# xv11_lidar_controller.net
KiCad netlist of a schematic drawn in EAGLE
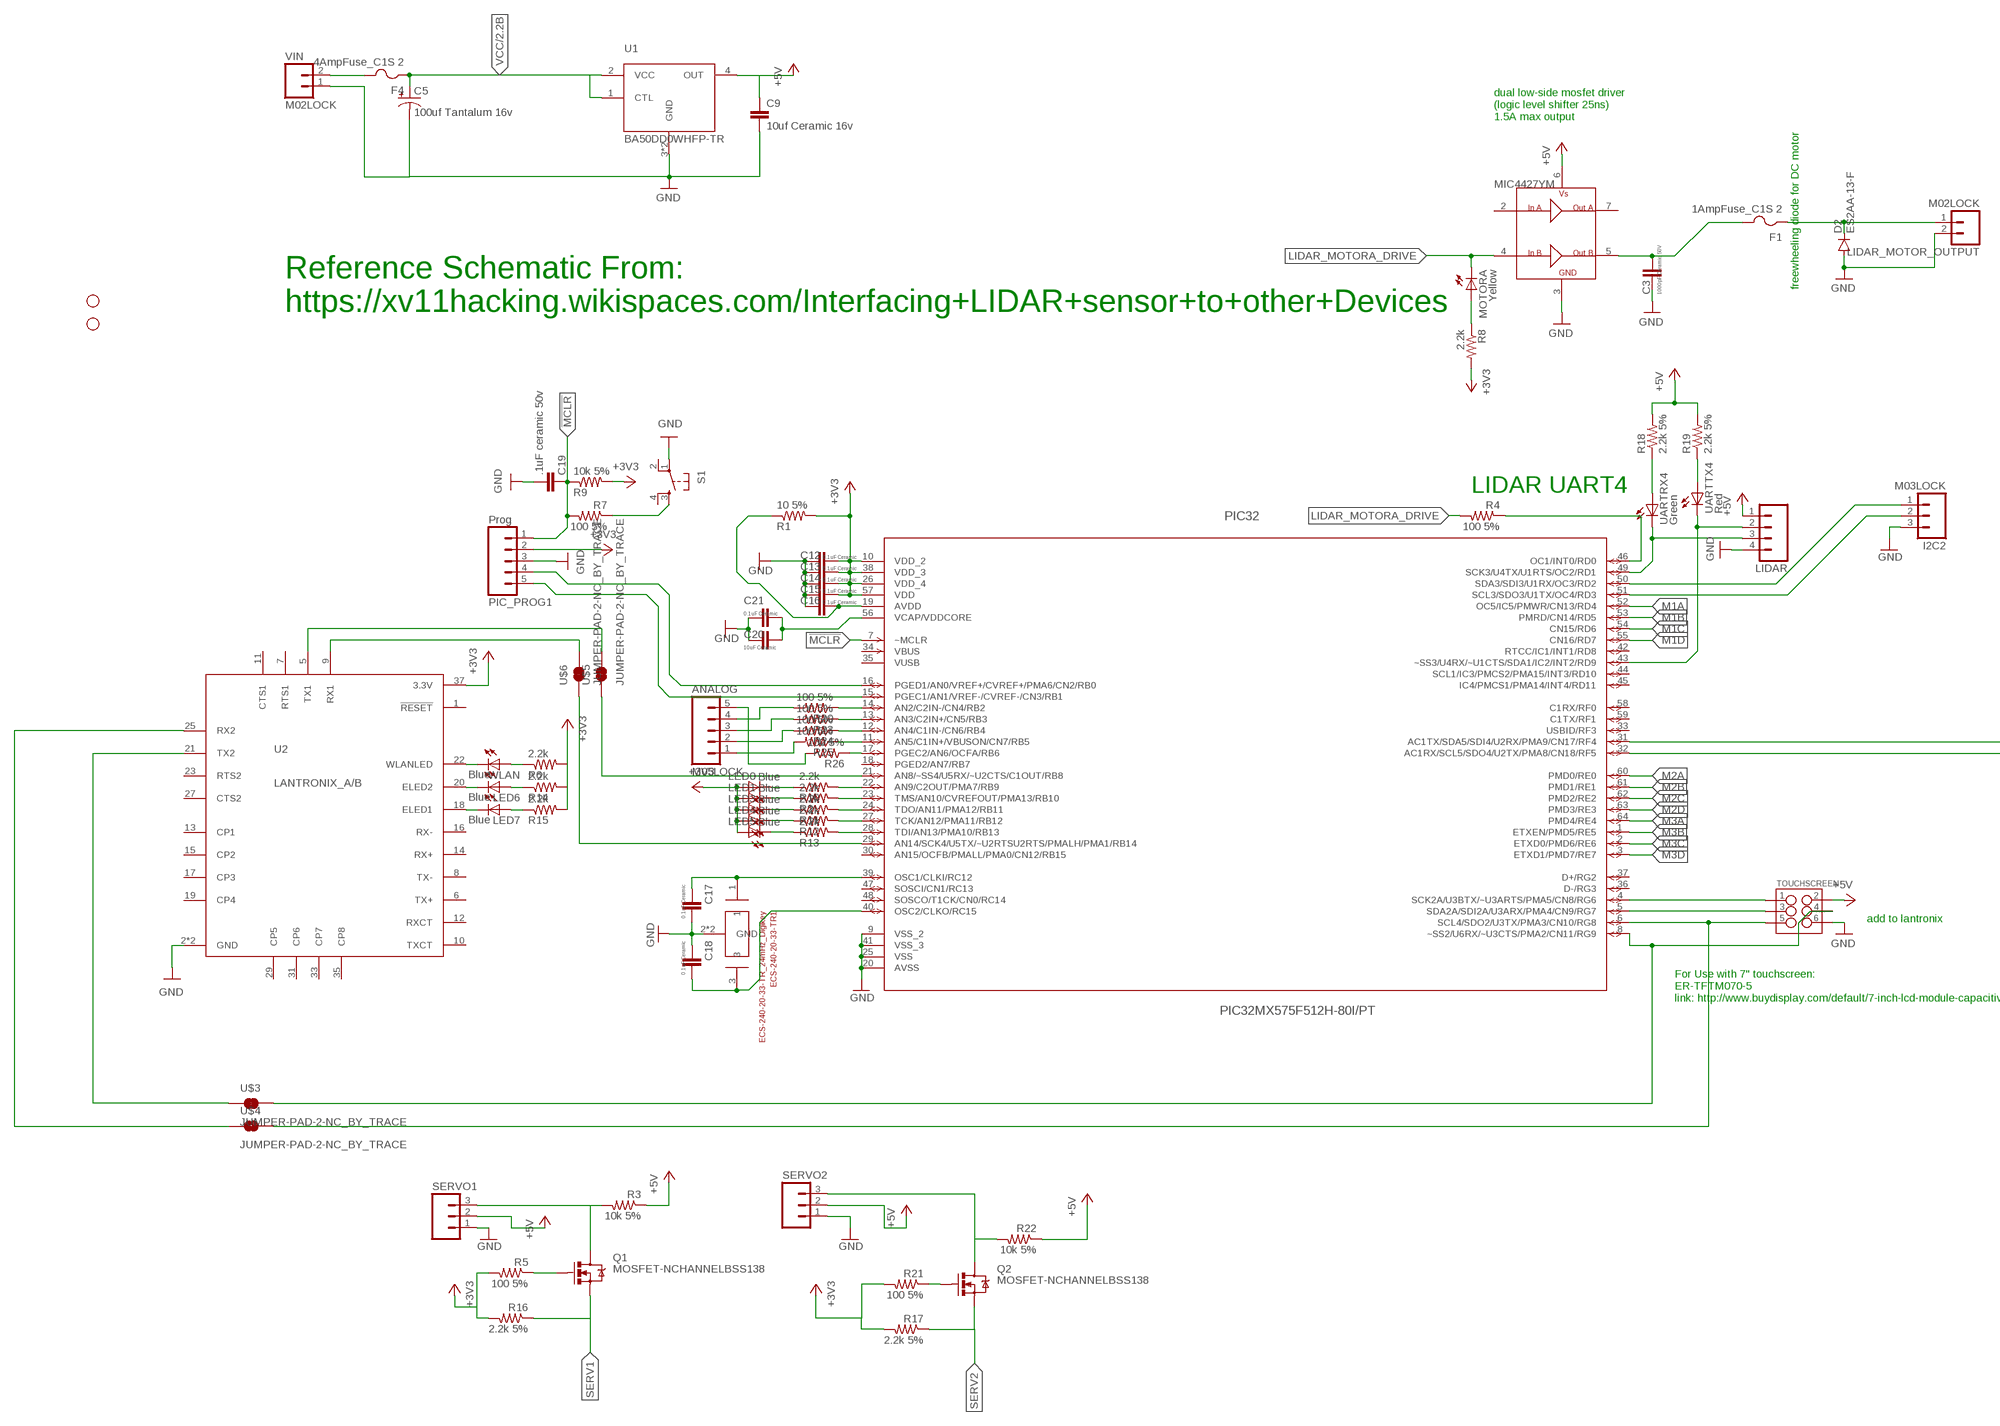
[diagram p0: schematic, sheet 1, part 1 of 2]
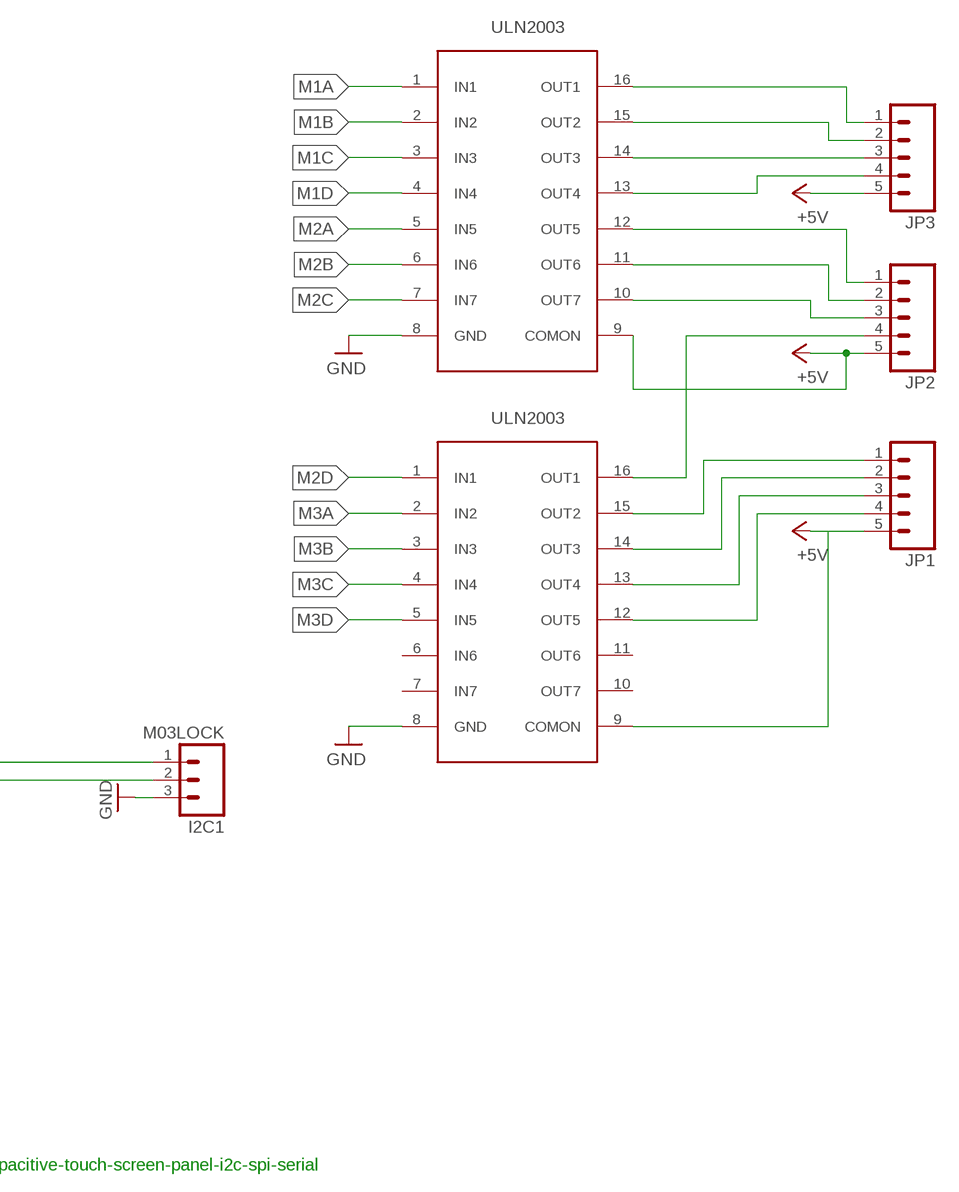
[diagram p1: schematic, sheet 1, part 2 of 2]
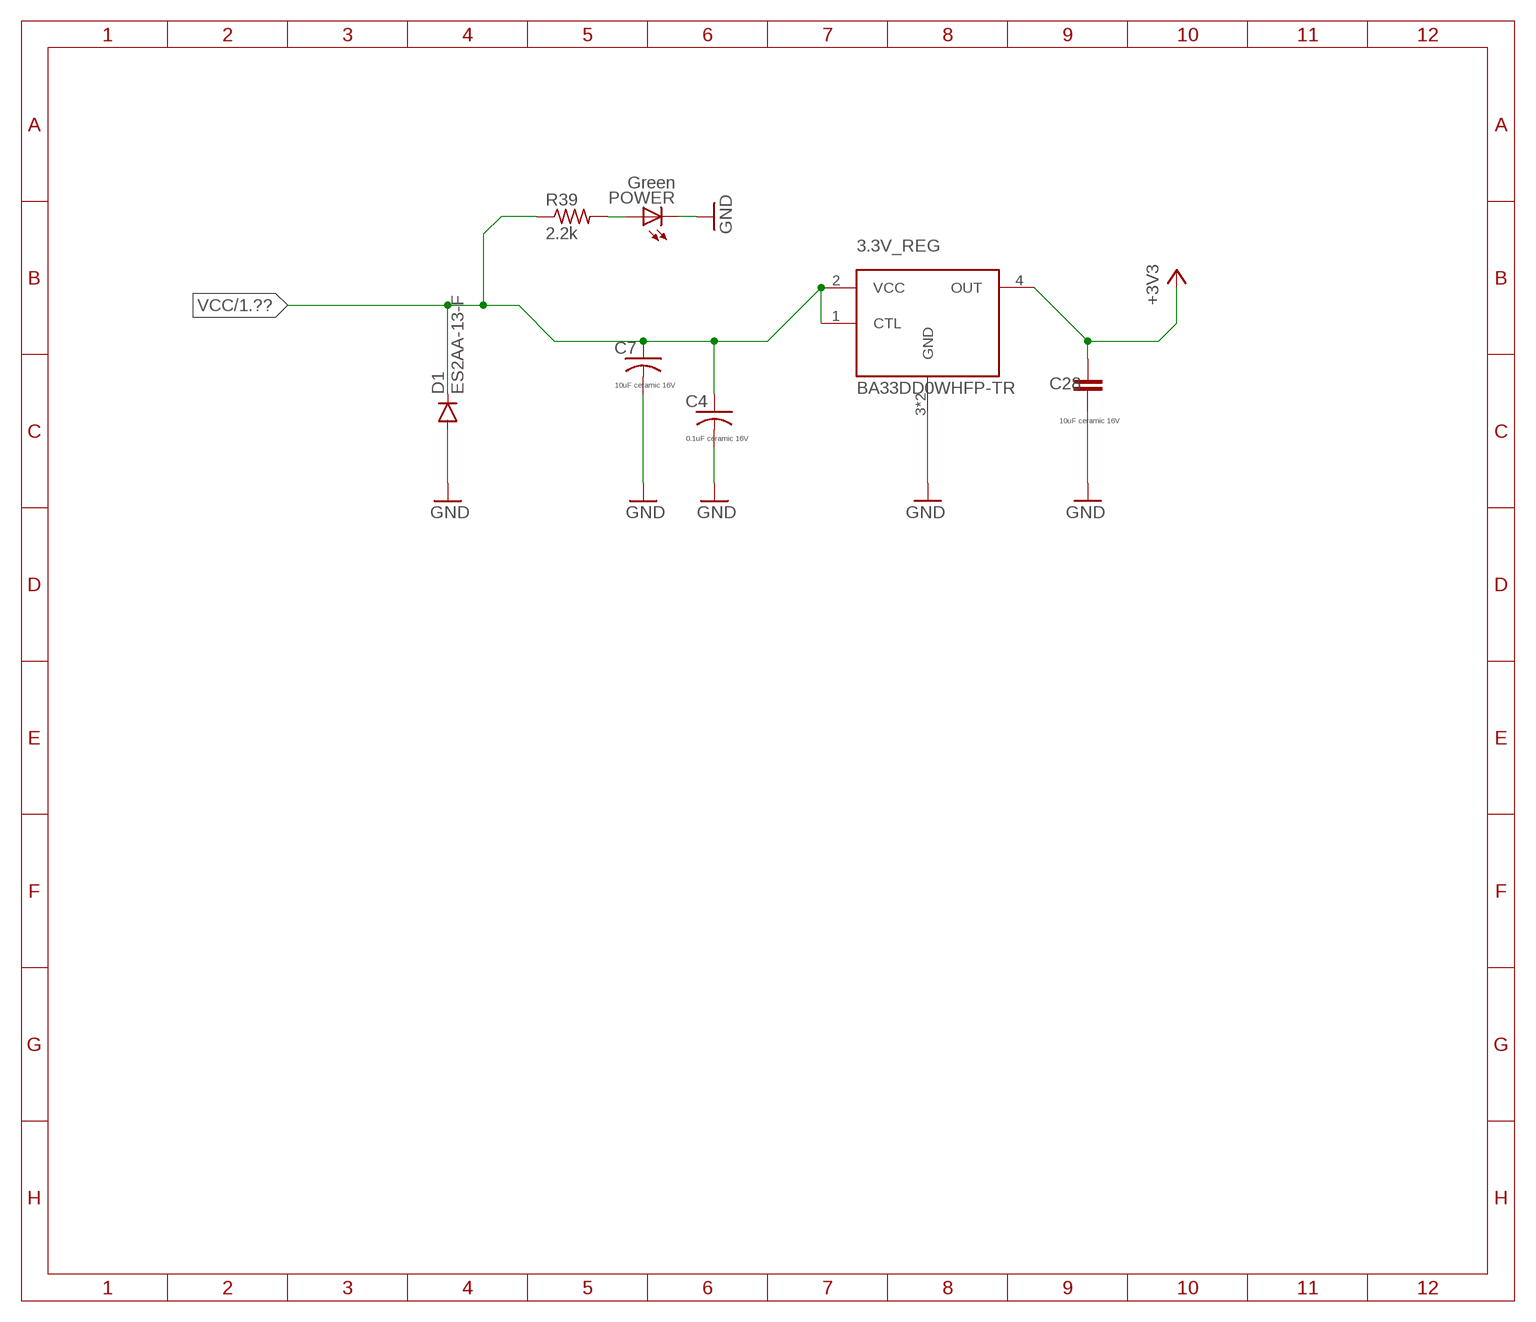
[diagram p2: schematic, sheet 2]

(export (version "E")
  (design (tool "Eeschema 10.0.6"))
  (components
    (comp (ref "3.3V_REG")
      (value "BA33DD0WHFP-TR")
      (footprint "eagle-import:HRP5")
      (libsource (lib "eagle-import") (part "BA50DD0WHFP-TR"))
    )
    (comp (ref "C4")
      (value "0.1uF ceramic 16V")
      (footprint "eagle-import:C0805K")
      (libsource (lib "eagle-import") (part "C-USC0805K"))
    )
    (comp (ref "C7")
      (value "10uF ceramic 16V")
      (footprint "eagle-import:C0805K")
      (libsource (lib "eagle-import") (part "C-USC0805K"))
    )
    (comp (ref "C28")
      (value "10uF ceramic 16V")
      (footprint "eagle-import:0805")
      (libsource (lib "eagle-import") (part "CAP0805"))
    )
    (comp (ref "D1")
      (value "ES2AA-13-F")
      (footprint "eagle-import:SMA-DIODE")
      (libsource (lib "eagle-import") (part "DIODESMA"))
    )
    (comp (ref "POWER")
      (value "Green")
      (footprint "eagle-import:CHIP-LED0805")
      (libsource (lib "eagle-import") (part "LEDCHIP-LED0805"))
    )
    (comp (ref "R39")
      (value "2.2k")
      (footprint "eagle-import:R0805")
      (libsource (lib "eagle-import") (part "R-US_R0805"))
    )
    (comp (ref "ANALOG")
      (value "M05LOCK")
      (footprint "eagle-import:1X05_LOCK")
      (libsource (lib "eagle-import") (part "M05LOCK"))
    )
    (comp (ref "C3")
      (value "1000pF Ceramic 50V")
      (footprint "eagle-import:0805")
      (libsource (lib "eagle-import") (part "CAP0805"))
    )
    (comp (ref "C5")
      (value "100uf Tantalum 16v")
      (footprint "eagle-import:EIA3216")
      (libsource (lib "eagle-import") (part "CAP_POL1206"))
    )
    (comp (ref "C9")
      (value "10uf Ceramic 16v")
      (footprint "eagle-import:0805")
      (libsource (lib "eagle-import") (part "CAP0805"))
    )
    (comp (ref "C12")
      (value "0.1uF Ceramic")
      (footprint "eagle-import:0805")
      (libsource (lib "eagle-import") (part "CAP0805"))
    )
    (comp (ref "C13")
      (value "0.1uF Ceramic")
      (footprint "eagle-import:0805")
      (libsource (lib "eagle-import") (part "CAP0805"))
    )
    (comp (ref "C14")
      (value "0.1uF Ceramic")
      (footprint "eagle-import:0805")
      (libsource (lib "eagle-import") (part "CAP0805"))
    )
    (comp (ref "C15")
      (value "0.1uF Ceramic")
      (footprint "eagle-import:0805")
      (libsource (lib "eagle-import") (part "CAP0805"))
    )
    (comp (ref "C16")
      (value "0.1uF Ceramic")
      (footprint "eagle-import:0805")
      (libsource (lib "eagle-import") (part "CAP0805"))
    )
    (comp (ref "C17")
      (value "0.1uF Ceramic")
      (footprint "eagle-import:0805")
      (libsource (lib "eagle-import") (part "CAP0805"))
    )
    (comp (ref "C18")
      (value "0.1uF Ceramic")
      (footprint "eagle-import:0805")
      (libsource (lib "eagle-import") (part "CAP0805"))
    )
    (comp (ref "C19")
      (value ".1uF ceramic 50v")
      (footprint "eagle-import:0805")
      (libsource (lib "eagle-import") (part "1UF-25V-10%(0805)"))
    )
    (comp (ref "C20")
      (value "10uF Ceramic")
      (footprint "eagle-import:0805")
      (libsource (lib "eagle-import") (part "CAP0805"))
    )
    (comp (ref "C21")
      (value "0.1uF Ceramic")
      (footprint "eagle-import:0805")
      (libsource (lib "eagle-import") (part "CAP0805"))
    )
    (comp (ref "D2")
      (value "ES2AA-13-F")
      (footprint "eagle-import:SMA-DIODE")
      (libsource (lib "eagle-import") (part "DIODESMA"))
    )
    (comp (ref "ECS-240-20-33-TR1")
      (value "ECS-240-20-33-TR_24mHz_Digikey")
      (footprint "eagle-import:ECX-32")
      (libsource (lib "eagle-import") (part "CRYSTAL"))
    )
    (comp (ref "F1")
      (value "1AmpFuse_C1S 2")
      (footprint "eagle-import:R1206")
      (libsource (lib "eagle-import") (part "PTCFUSE-1206"))
    )
    (comp (ref "F4")
      (value "4AmpFuse_C1S 2")
      (footprint "eagle-import:R1206")
      (libsource (lib "eagle-import") (part "PTCFUSE-1206"))
    )
    (comp (ref "I2C1")
      (value "M03LOCK")
      (footprint "eagle-import:1X03_LOCK")
      (libsource (lib "eagle-import") (part "M03LOCK"))
    )
    (comp (ref "I2C2")
      (value "M03LOCK")
      (footprint "eagle-import:1X03_LOCK")
      (libsource (lib "eagle-import") (part "M03LOCK"))
    )
    (comp (ref "JP1")
      (value "M05LOCK")
      (footprint "eagle-import:1X05_LOCK")
      (libsource (lib "eagle-import") (part "M05LOCK"))
    )
    (comp (ref "JP2")
      (value "M05LOCK")
      (footprint "eagle-import:1X05_LOCK")
      (libsource (lib "eagle-import") (part "M05LOCK"))
    )
    (comp (ref "JP3")
      (value "M05LOCK")
      (footprint "eagle-import:1X05_LOCK")
      (libsource (lib "eagle-import") (part "M05LOCK"))
    )
    (comp (ref "LED0")
      (value "Blue")
      (footprint "eagle-import:CHIP-LED0805")
      (libsource (lib "eagle-import") (part "LEDCHIP-LED0805"))
    )
    (comp (ref "LED1")
      (value "Blue")
      (footprint "eagle-import:CHIP-LED0805")
      (libsource (lib "eagle-import") (part "LEDCHIP-LED0805"))
    )
    (comp (ref "LED3")
      (value "Blue")
      (footprint "eagle-import:CHIP-LED0805")
      (libsource (lib "eagle-import") (part "LEDCHIP-LED0805"))
    )
    (comp (ref "LED4")
      (value "Blue")
      (footprint "eagle-import:CHIP-LED0805")
      (libsource (lib "eagle-import") (part "LEDCHIP-LED0805"))
    )
    (comp (ref "LED5")
      (value "Blue")
      (footprint "eagle-import:CHIP-LED0805")
      (libsource (lib "eagle-import") (part "LEDCHIP-LED0805"))
    )
    (comp (ref "LED6")
      (value "Blue")
      (footprint "eagle-import:CHIP-LED0805")
      (libsource (lib "eagle-import") (part "LEDCHIP-LED0805"))
    )
    (comp (ref "LED7")
      (value "Blue")
      (footprint "eagle-import:CHIP-LED0805")
      (libsource (lib "eagle-import") (part "LEDCHIP-LED0805"))
    )
    (comp (ref "LIDAR")
      (value "M04LOCK")
      (footprint "eagle-import:1X04_LOCK")
      (libsource (lib "eagle-import") (part "M04LOCK"))
    )
    (comp (ref "LIDAR_MOTOR_OUTPUT")
      (value "M02LOCK")
      (footprint "eagle-import:1X02_LOCK")
      (libsource (lib "eagle-import") (part "M02LOCK"))
    )
    (comp (ref "MOTORA")
      (value "Yellow")
      (footprint "eagle-import:CHIP-LED0805")
      (libsource (lib "eagle-import") (part "LEDCHIP-LED0805"))
    )
    (comp (ref "PIC32")
      (value "PIC32MX575F512H-80I/PT")
      (footprint "eagle-import:QFP50P1200X1200X120-64N")
      (fields (field (name "MPN") "PIC32MX675F512H-80I/PT"))
      (libsource (lib "eagle-import") (part "PIC32MX575F512H-80I/PT"))
    )
    (comp (ref "PIC_PROG1")
      (value "Prog")
      (footprint "eagle-import:1X05_LOCK_LONGPADS")
      (libsource (lib "eagle-import") (part "M05LOCK_LONGPADS"))
    )
    (comp (ref "Q1")
      (value "MOSFET-NCHANNELBSS138")
      (footprint "eagle-import:SOT23")
      (libsource (lib "eagle-import") (part "MOSFET-NCHANNELBSS138"))
    )
    (comp (ref "Q2")
      (value "MOSFET-NCHANNELBSS138")
      (footprint "eagle-import:SOT23")
      (libsource (lib "eagle-import") (part "MOSFET-NCHANNELBSS138"))
    )
    (comp (ref "R1")
      (value "10 5%")
      (footprint "eagle-import:R0805")
      (libsource (lib "eagle-import") (part "R-US_R0805"))
    )
    (comp (ref "R2")
      (value "2.2k")
      (footprint "eagle-import:R0805")
      (libsource (lib "eagle-import") (part "R-US_R0805"))
    )
    (comp (ref "R3")
      (value "10k 5%")
      (footprint "eagle-import:R0805")
      (libsource (lib "eagle-import") (part "R-US_R0805"))
    )
    (comp (ref "R4")
      (value "100 5%")
      (footprint "eagle-import:M0805")
      (libsource (lib "eagle-import") (part "R-US_M0805"))
    )
    (comp (ref "R5")
      (value "100 5%")
      (footprint "eagle-import:R0805")
      (libsource (lib "eagle-import") (part "R-US_R0805"))
    )
    (comp (ref "R6")
      (value "2.2k")
      (footprint "eagle-import:R0805")
      (libsource (lib "eagle-import") (part "R-US_R0805"))
    )
    (comp (ref "R7")
      (value "100 5%")
      (footprint "eagle-import:R0805")
      (libsource (lib "eagle-import") (part "R-US_R0805"))
    )
    (comp (ref "R8")
      (value "2.2k")
      (footprint "eagle-import:M0805")
      (libsource (lib "eagle-import") (part "R-US_M0805"))
    )
    (comp (ref "R9")
      (value "10k 5%")
      (footprint "eagle-import:R0805")
      (libsource (lib "eagle-import") (part "R-US_R0805"))
    )
    (comp (ref "R10")
      (value "2.2k")
      (footprint "eagle-import:R0805")
      (libsource (lib "eagle-import") (part "R-US_R0805"))
    )
    (comp (ref "R11")
      (value "2.2k")
      (footprint "eagle-import:R0805")
      (libsource (lib "eagle-import") (part "R-US_R0805"))
    )
    (comp (ref "R12")
      (value "2.2k")
      (footprint "eagle-import:R0805")
      (libsource (lib "eagle-import") (part "R-US_R0805"))
    )
    (comp (ref "R13")
      (value "2.2k")
      (footprint "eagle-import:R0805")
      (libsource (lib "eagle-import") (part "R-US_R0805"))
    )
    (comp (ref "R14")
      (value "2.2k")
      (footprint "eagle-import:R0805")
      (libsource (lib "eagle-import") (part "R-US_R0805"))
    )
    (comp (ref "R15")
      (value "2.2k")
      (footprint "eagle-import:R0805")
      (libsource (lib "eagle-import") (part "R-US_R0805"))
    )
    (comp (ref "R16")
      (value "2.2k 5%")
      (footprint "eagle-import:R0805")
      (libsource (lib "eagle-import") (part "R-US_R0805"))
    )
    (comp (ref "R17")
      (value "2.2k 5%")
      (footprint "eagle-import:R0805")
      (libsource (lib "eagle-import") (part "R-US_R0805"))
    )
    (comp (ref "R18")
      (value "2.2k 5%")
      (footprint "eagle-import:M0805")
      (libsource (lib "eagle-import") (part "R-US_M0805"))
    )
    (comp (ref "R19")
      (value "2.2k 5%")
      (footprint "eagle-import:M0805")
      (libsource (lib "eagle-import") (part "R-US_M0805"))
    )
    (comp (ref "R20")
      (value "100 5%")
      (footprint "eagle-import:R0805")
      (libsource (lib "eagle-import") (part "R-US_R0805"))
    )
    (comp (ref "R21")
      (value "100 5%")
      (footprint "eagle-import:R0805")
      (libsource (lib "eagle-import") (part "R-US_R0805"))
    )
    (comp (ref "R22")
      (value "10k 5%")
      (footprint "eagle-import:R0805")
      (libsource (lib "eagle-import") (part "R-US_R0805"))
    )
    (comp (ref "R23")
      (value "100 5%")
      (footprint "eagle-import:R0805")
      (libsource (lib "eagle-import") (part "R-US_R0805"))
    )
    (comp (ref "R24")
      (value "100 5%")
      (footprint "eagle-import:R0805")
      (libsource (lib "eagle-import") (part "R-US_R0805"))
    )
    (comp (ref "R25")
      (value "100 5%")
      (footprint "eagle-import:R0805")
      (libsource (lib "eagle-import") (part "R-US_R0805"))
    )
    (comp (ref "R26")
      (value "100 5%")
      (footprint "eagle-import:R0805")
      (libsource (lib "eagle-import") (part "R-US_R0805"))
    )
    (comp (ref "S1")
      (value "TAC_SWITCHSMD")
      (footprint "eagle-import:TACTILE-SWITCH-SMD")
      (libsource (lib "eagle-import") (part "TAC_SWITCHSMD"))
    )
    (comp (ref "SERVO1")
      (value "M03PTH")
      (footprint "eagle-import:1X03")
      (libsource (lib "eagle-import") (part "M03PTH"))
    )
    (comp (ref "SERVO2")
      (value "M03PTH")
      (footprint "eagle-import:1X03")
      (libsource (lib "eagle-import") (part "M03PTH"))
    )
    (comp (ref "STANDOFF1")
      (value "STAND-OFF")
      (footprint "eagle-import:STAND-OFF")
      (libsource (lib "eagle-import") (part "STAND-OFF"))
    )
    (comp (ref "STANDOFF2")
      (value "STAND-OFF")
      (footprint "eagle-import:STAND-OFF")
      (libsource (lib "eagle-import") (part "STAND-OFF"))
    )
    (comp (ref "TOUCHSCREEN")
      (value "M03X2NO_SILK")
      (footprint "eagle-import:2X3-NS")
      (libsource (lib "eagle-import") (part "M03X2NO_SILK"))
    )
    (comp (ref "U$1")
      (value "ULN2003")
      (footprint "eagle-import:SOIC16_3.9WIDE")
      (libsource (lib "eagle-import") (part "ULN2003"))
    )
    (comp (ref "U$2")
      (value "ULN2003")
      (footprint "eagle-import:SOIC16_3.9WIDE")
      (libsource (lib "eagle-import") (part "ULN2003"))
    )
    (comp (ref "U$3")
      (value "JUMPER-PAD-2-NC_BY_TRACE")
      (footprint "eagle-import:PAD-JUMPER-2-NC_BY_TRACE_YES_SILK")
      (libsource (lib "eagle-import") (part "JUMPER-PAD-2-NC_BY_TRACE"))
    )
    (comp (ref "U$4")
      (value "JUMPER-PAD-2-NC_BY_TRACE")
      (footprint "eagle-import:PAD-JUMPER-2-NC_BY_TRACE_YES_SILK")
      (libsource (lib "eagle-import") (part "JUMPER-PAD-2-NC_BY_TRACE"))
    )
    (comp (ref "U$5")
      (value "JUMPER-PAD-2-NC_BY_TRACE")
      (footprint "eagle-import:PAD-JUMPER-2-NC_BY_TRACE_YES_SILK")
      (libsource (lib "eagle-import") (part "JUMPER-PAD-2-NC_BY_TRACE"))
    )
    (comp (ref "U$6")
      (value "JUMPER-PAD-2-NC_BY_TRACE")
      (footprint "eagle-import:PAD-JUMPER-2-NC_BY_TRACE_YES_SILK")
      (libsource (lib "eagle-import") (part "JUMPER-PAD-2-NC_BY_TRACE"))
    )
    (comp (ref "U1")
      (value "BA50DD0WHFP-TR")
      (footprint "eagle-import:HRP5")
      (libsource (lib "eagle-import") (part "BA50DD0WHFP-TR"))
    )
    (comp (ref "U2")
      (value "LANTRONIX_A/B")
      (footprint "eagle-import:LANA_BTH")
      (libsource (lib "eagle-import") (part "LANTRONIX_A/B"))
    )
    (comp (ref "U3")
      (value "MIC4427YM")
      (footprint "eagle-import:SO-08")
      (libsource (lib "eagle-import") (part "MIC4427YM"))
    )
    (comp (ref "UARTRX4")
      (value "Green")
      (footprint "eagle-import:CHIP-LED0805")
      (libsource (lib "eagle-import") (part "LEDCHIP-LED0805"))
    )
    (comp (ref "UARTTX4")
      (value "Red")
      (footprint "eagle-import:CHIP-LED0805")
      (libsource (lib "eagle-import") (part "LEDCHIP-LED0805"))
    )
    (comp (ref "VIN")
      (value "M02LOCK")
      (footprint "eagle-import:1X02_LOCK")
      (libsource (lib "eagle-import") (part "M02LOCK"))
    )
    (comp (ref "WLAN")
      (value "Blue")
      (footprint "eagle-import:CHIP-LED0805")
      (libsource (lib "eagle-import") (part "LEDCHIP-LED0805"))
    )
  )
  (nets
    (net (code "1") (name "+3V3") (class "Default")
      (node (ref "3.3V_REG") (pin "4") (pinfunction "OUT_4") (pintype "bidirectional"))
      (node (ref "C12") (pin "2") (pinfunction "2_2") (pintype "passive"))
      (node (ref "C13") (pin "2") (pinfunction "2_2") (pintype "passive"))
      (node (ref "C14") (pin "2") (pinfunction "2_2") (pintype "passive"))
      (node (ref "C15") (pin "2") (pinfunction "2_2") (pintype "passive"))
      (node (ref "C28") (pin "1") (pinfunction "1_1") (pintype "passive"))
      (node (ref "LED0") (pin "A") (pinfunction "A_A") (pintype "passive"))
      (node (ref "LED1") (pin "A") (pinfunction "A_A") (pintype "passive"))
      (node (ref "LED3") (pin "A") (pinfunction "A_A") (pintype "passive"))
      (node (ref "LED4") (pin "A") (pinfunction "A_A") (pintype "passive"))
      (node (ref "LED5") (pin "A") (pinfunction "A_A") (pintype "passive"))
      (node (ref "PIC32") (pin "10") (pinfunction "VDD_2_10") (pintype "power_in"))
      (node (ref "PIC32") (pin "26") (pinfunction "VDD_4_26") (pintype "power_in"))
      (node (ref "PIC32") (pin "38") (pinfunction "VDD_3_38") (pintype "power_in"))
      (node (ref "PIC32") (pin "57") (pinfunction "VDD_57") (pintype "power_in"))
      (node (ref "PIC_PROG1") (pin "2") (pinfunction "2_2") (pintype "passive"))
      (node (ref "R1") (pin "2") (pinfunction "2_2") (pintype "passive"))
      (node (ref "R14") (pin "2") (pinfunction "2_2") (pintype "passive"))
      (node (ref "R15") (pin "2") (pinfunction "2_2") (pintype "passive"))
      (node (ref "R16") (pin "2") (pinfunction "2_2") (pintype "passive"))
      (node (ref "R17") (pin "2") (pinfunction "2_2") (pintype "passive"))
      (node (ref "R21") (pin "2") (pinfunction "2_2") (pintype "passive"))
      (node (ref "R5") (pin "2") (pinfunction "2_2") (pintype "passive"))
      (node (ref "R6") (pin "2") (pinfunction "2_2") (pintype "passive"))
      (node (ref "R8") (pin "2") (pinfunction "2_2") (pintype "passive"))
      (node (ref "R9") (pin "2") (pinfunction "2_2") (pintype "passive"))
      (node (ref "U2") (pin "37") (pinfunction "3.3V_37") (pintype "bidirectional"))
    )
    (net (code "2") (name "+5V") (class "Default")
      (node (ref "C9") (pin "1") (pinfunction "1_1") (pintype "passive"))
      (node (ref "JP1") (pin "5") (pinfunction "5_5") (pintype "passive"))
      (node (ref "JP2") (pin "5") (pinfunction "5_5") (pintype "passive"))
      (node (ref "JP3") (pin "5") (pinfunction "5_5") (pintype "passive"))
      (node (ref "LIDAR") (pin "1") (pinfunction "1_1") (pintype "passive"))
      (node (ref "R18") (pin "2") (pinfunction "2_2") (pintype "passive"))
      (node (ref "R19") (pin "2") (pinfunction "2_2") (pintype "passive"))
      (node (ref "R22") (pin "1") (pinfunction "1_1") (pintype "passive"))
      (node (ref "R3") (pin "1") (pinfunction "1_1") (pintype "passive"))
      (node (ref "SERVO1") (pin "2") (pinfunction "2_2") (pintype "passive"))
      (node (ref "SERVO2") (pin "2") (pinfunction "2_2") (pintype "passive"))
      (node (ref "TOUCHSCREEN") (pin "2") (pinfunction "2_2") (pintype "bidirectional"))
      (node (ref "U$1") (pin "9") (pinfunction "COMON_9") (pintype "bidirectional"))
      (node (ref "U$2") (pin "9") (pinfunction "COMON_9") (pintype "bidirectional"))
      (node (ref "U1") (pin "4") (pinfunction "OUT_4") (pintype "bidirectional"))
      (node (ref "U3") (pin "6") (pinfunction "VS_6") (pintype "bidirectional"))
    )
    (net (code "3") (name "GND") (class "Default")
      (node (ref "3.3V_REG") (pin "3") (pinfunction "GND_3") (pintype "bidirectional"))
      (node (ref "3.3V_REG") (pin "G") (pinfunction "GND_G") (pintype "bidirectional"))
      (node (ref "C12") (pin "1") (pinfunction "1_1") (pintype "passive"))
      (node (ref "C13") (pin "1") (pinfunction "1_1") (pintype "passive"))
      (node (ref "C14") (pin "1") (pinfunction "1_1") (pintype "passive"))
      (node (ref "C15") (pin "1") (pinfunction "1_1") (pintype "passive"))
      (node (ref "C16") (pin "1") (pinfunction "1_1") (pintype "passive"))
      (node (ref "C17") (pin "2") (pinfunction "2_2") (pintype "passive"))
      (node (ref "C18") (pin "1") (pinfunction "1_1") (pintype "passive"))
      (node (ref "C19") (pin "2") (pinfunction "2_2") (pintype "passive"))
      (node (ref "C20") (pin "1") (pinfunction "1_1") (pintype "passive"))
      (node (ref "C21") (pin "1") (pinfunction "1_1") (pintype "passive"))
      (node (ref "C28") (pin "2") (pinfunction "2_2") (pintype "passive"))
      (node (ref "C3") (pin "1") (pinfunction "1_1") (pintype "passive"))
      (node (ref "C4") (pin "2") (pinfunction "2_2") (pintype "passive"))
      (node (ref "C5") (pin "C") (pinfunction "-_C") (pintype "passive"))
      (node (ref "C7") (pin "2") (pinfunction "2_2") (pintype "passive"))
      (node (ref "C9") (pin "2") (pinfunction "2_2") (pintype "passive"))
      (node (ref "D1") (pin "A") (pinfunction "A_A") (pintype "passive"))
      (node (ref "D2") (pin "A") (pinfunction "A_A") (pintype "passive"))
      (node (ref "ECS-240-20-33-TR1") (pin "2") (pinfunction "GND_2") (pintype "bidirectional"))
      (node (ref "ECS-240-20-33-TR1") (pin "4") (pinfunction "GND_4") (pintype "bidirectional"))
      (node (ref "I2C1") (pin "3") (pinfunction "3_3") (pintype "passive"))
      (node (ref "I2C2") (pin "3") (pinfunction "3_3") (pintype "passive"))
      (node (ref "LIDAR") (pin "4") (pinfunction "4_4") (pintype "passive"))
      (node (ref "LIDAR_MOTOR_OUTPUT") (pin "2") (pinfunction "2_2") (pintype "passive"))
      (node (ref "PIC32") (pin "20") (pinfunction "AVSS_20") (pintype "power_in"))
      (node (ref "PIC32") (pin "25") (pinfunction "VSS_25") (pintype "power_in"))
      (node (ref "PIC32") (pin "41") (pinfunction "VSS_3_41") (pintype "power_in"))
      (node (ref "PIC32") (pin "9") (pinfunction "VSS_2_9") (pintype "power_in"))
      (node (ref "PIC_PROG1") (pin "3") (pinfunction "3_3") (pintype "passive"))
      (node (ref "POWER") (pin "C") (pinfunction "C_C") (pintype "passive"))
      (node (ref "S1") (pin "1") (pinfunction "1_1") (pintype "passive"))
      (node (ref "SERVO1") (pin "1") (pinfunction "1_1") (pintype "passive"))
      (node (ref "SERVO2") (pin "1") (pinfunction "1_1") (pintype "passive"))
      (node (ref "TOUCHSCREEN") (pin "6") (pinfunction "6_6") (pintype "bidirectional"))
      (node (ref "U$1") (pin "8") (pinfunction "GND_8") (pintype "bidirectional"))
      (node (ref "U$2") (pin "8") (pinfunction "GND_8") (pintype "bidirectional"))
      (node (ref "U1") (pin "3") (pinfunction "GND_3") (pintype "bidirectional"))
      (node (ref "U1") (pin "G") (pinfunction "GND_G") (pintype "bidirectional"))
      (node (ref "U2") (pin "2") (pinfunction "GND_2") (pintype "bidirectional"))
      (node (ref "U2") (pin "39") (pinfunction "GND_39") (pintype "bidirectional"))
      (node (ref "U3") (pin "3") (pinfunction "GND_3") (pintype "bidirectional"))
      (node (ref "VIN") (pin "1") (pinfunction "1_1") (pintype "passive"))
    )
    (net (code "4") (name "LIDAR_MOTORA_DRIVE") (class "Default")
      (node (ref "MOTORA") (pin "C") (pinfunction "C_C") (pintype "passive"))
      (node (ref "R4") (pin "2") (pinfunction "2_2") (pintype "passive"))
      (node (ref "U3") (pin "4") (pinfunction "INB_4") (pintype "bidirectional"))
    )
    (net (code "5") (name "M1A") (class "Default")
      (node (ref "PIC32") (pin "52") (pinfunction "OC5/IC5/PMWR/CN13/RD4_52") (pintype "bidirectional"))
      (node (ref "U$1") (pin "1") (pinfunction "IN1_1") (pintype "bidirectional"))
    )
    (net (code "6") (name "M1B") (class "Default")
      (node (ref "PIC32") (pin "53") (pinfunction "PMRD/CN14/RD5_53") (pintype "bidirectional"))
      (node (ref "U$1") (pin "2") (pinfunction "IN2_2") (pintype "bidirectional"))
    )
    (net (code "7") (name "M1C") (class "Default")
      (node (ref "PIC32") (pin "54") (pinfunction "CN15/RD6_54") (pintype "bidirectional"))
      (node (ref "U$1") (pin "3") (pinfunction "IN3_3") (pintype "bidirectional"))
    )
    (net (code "8") (name "M1D") (class "Default")
      (node (ref "PIC32") (pin "55") (pinfunction "CN16/RD7_55") (pintype "bidirectional"))
      (node (ref "U$1") (pin "4") (pinfunction "IN4_4") (pintype "bidirectional"))
    )
    (net (code "9") (name "M2A") (class "Default")
      (node (ref "PIC32") (pin "60") (pinfunction "PMD0/RE0_60") (pintype "bidirectional"))
      (node (ref "U$1") (pin "5") (pinfunction "IN5_5") (pintype "bidirectional"))
    )
    (net (code "10") (name "M2B") (class "Default")
      (node (ref "PIC32") (pin "61") (pinfunction "PMD1/RE1_61") (pintype "bidirectional"))
      (node (ref "U$1") (pin "6") (pinfunction "IN6_6") (pintype "bidirectional"))
    )
    (net (code "11") (name "M2C") (class "Default")
      (node (ref "PIC32") (pin "62") (pinfunction "PMD2/RE2_62") (pintype "bidirectional"))
      (node (ref "U$1") (pin "7") (pinfunction "IN7_7") (pintype "bidirectional"))
    )
    (net (code "12") (name "M2D") (class "Default")
      (node (ref "PIC32") (pin "63") (pinfunction "PMD3/RE3_63") (pintype "bidirectional"))
      (node (ref "U$2") (pin "1") (pinfunction "IN1_1") (pintype "bidirectional"))
    )
    (net (code "13") (name "M3A") (class "Default")
      (node (ref "PIC32") (pin "64") (pinfunction "PMD4/RE4_64") (pintype "bidirectional"))
      (node (ref "U$2") (pin "2") (pinfunction "IN2_2") (pintype "bidirectional"))
    )
    (net (code "14") (name "M3B") (class "Default")
      (node (ref "PIC32") (pin "1") (pinfunction "ETXEN/PMD5/RE5_1") (pintype "bidirectional"))
      (node (ref "U$2") (pin "3") (pinfunction "IN3_3") (pintype "bidirectional"))
    )
    (net (code "15") (name "M3C") (class "Default")
      (node (ref "PIC32") (pin "2") (pinfunction "ETXD0/PMD6/RE6_2") (pintype "bidirectional"))
      (node (ref "U$2") (pin "4") (pinfunction "IN4_4") (pintype "bidirectional"))
    )
    (net (code "16") (name "M3D") (class "Default")
      (node (ref "PIC32") (pin "3") (pinfunction "ETXD1/PMD7/RE7_3") (pintype "bidirectional"))
      (node (ref "U$2") (pin "5") (pinfunction "IN5_5") (pintype "bidirectional"))
    )
    (net (code "17") (name "Net-(ANALOG-Pad1)") (class "Default")
      (node (ref "ANALOG") (pin "1") (pinfunction "1_1") (pintype "passive"))
      (node (ref "R25") (pin "2") (pinfunction "2_2") (pintype "passive"))
    )
    (net (code "18") (name "Net-(ANALOG-Pad2)") (class "Default")
      (node (ref "ANALOG") (pin "2") (pinfunction "2_2") (pintype "passive"))
      (node (ref "R24") (pin "2") (pinfunction "2_2") (pintype "passive"))
    )
    (net (code "19") (name "Net-(ANALOG-Pad3)") (class "Default")
      (node (ref "ANALOG") (pin "3") (pinfunction "3_3") (pintype "passive"))
      (node (ref "R23") (pin "2") (pinfunction "2_2") (pintype "passive"))
    )
    (net (code "20") (name "Net-(ANALOG-Pad4)") (class "Default")
      (node (ref "ANALOG") (pin "4") (pinfunction "4_4") (pintype "passive"))
      (node (ref "R20") (pin "2") (pinfunction "2_2") (pintype "passive"))
    )
    (net (code "21") (name "Net-(ANALOG-Pad5)") (class "Default")
      (node (ref "ANALOG") (pin "5") (pinfunction "5_5") (pintype "passive"))
      (node (ref "R26") (pin "2") (pinfunction "2_2") (pintype "passive"))
    )
    (net (code "22") (name "Net-(D2-PadC)") (class "Default")
      (node (ref "D2") (pin "C") (pinfunction "C_C") (pintype "passive"))
      (node (ref "F1") (pin "1") (pinfunction "1_1") (pintype "passive"))
      (node (ref "LIDAR_MOTOR_OUTPUT") (pin "1") (pinfunction "1_1") (pintype "passive"))
    )
    (net (code "23") (name "Net-(F4-Pad2)") (class "Default")
      (node (ref "F4") (pin "2") (pinfunction "2_2") (pintype "passive"))
      (node (ref "VIN") (pin "2") (pinfunction "2_2") (pintype "passive"))
    )
    (net (code "24") (name "Net-(LED0-PadC)") (class "Default")
      (node (ref "LED0") (pin "C") (pinfunction "C_C") (pintype "passive"))
      (node (ref "R10") (pin "1") (pinfunction "1_1") (pintype "passive"))
    )
    (net (code "25") (name "Net-(LED1-PadC)") (class "Default")
      (node (ref "LED1") (pin "C") (pinfunction "C_C") (pintype "passive"))
      (node (ref "R2") (pin "1") (pinfunction "1_1") (pintype "passive"))
    )
    (net (code "26") (name "Net-(LED3-PadC)") (class "Default")
      (node (ref "LED3") (pin "C") (pinfunction "C_C") (pintype "passive"))
      (node (ref "R11") (pin "1") (pinfunction "1_1") (pintype "passive"))
    )
    (net (code "27") (name "Net-(LED4-PadC)") (class "Default")
      (node (ref "LED4") (pin "C") (pinfunction "C_C") (pintype "passive"))
      (node (ref "R12") (pin "1") (pinfunction "1_1") (pintype "passive"))
    )
    (net (code "28") (name "Net-(LED5-PadC)") (class "Default")
      (node (ref "LED5") (pin "C") (pinfunction "C_C") (pintype "passive"))
      (node (ref "R13") (pin "1") (pinfunction "1_1") (pintype "passive"))
    )
    (net (code "29") (name "Net-(LED6-PadA)") (class "Default")
      (node (ref "LED6") (pin "A") (pinfunction "A_A") (pintype "passive"))
      (node (ref "R14") (pin "1") (pinfunction "1_1") (pintype "passive"))
    )
    (net (code "30") (name "Net-(LED7-PadA)") (class "Default")
      (node (ref "LED7") (pin "A") (pinfunction "A_A") (pintype "passive"))
      (node (ref "R15") (pin "1") (pinfunction "1_1") (pintype "passive"))
    )
    (net (code "31") (name "Net-(MOTORA-PadA)") (class "Default")
      (node (ref "MOTORA") (pin "A") (pinfunction "A_A") (pintype "passive"))
      (node (ref "R8") (pin "1") (pinfunction "1_1") (pintype "passive"))
    )
    (net (code "32") (name "Net-(PIC32-AC1RX{slash}SCL5{slash}SDO4{slash}U2TX{slash}PMA8{slash}CN18{slash}RF5)") (class "Default")
      (node (ref "I2C1") (pin "2") (pinfunction "2_2") (pintype "passive"))
      (node (ref "PIC32") (pin "32") (pinfunction "AC1RX/SCL5/SDO4/U2TX/PMA8/CN18/RF5_32") (pintype "bidirectional"))
    )
    (net (code "33") (name "Net-(PIC32-AC1TX{slash}SDA5{slash}SDI4{slash}U2RX{slash}PMA9{slash}CN17{slash}RF4)") (class "Default")
      (node (ref "I2C1") (pin "1") (pinfunction "1_1") (pintype "passive"))
      (node (ref "PIC32") (pin "31") (pinfunction "AC1TX/SDA5/SDI4/U2RX/PMA9/CN17/RF4_31") (pintype "bidirectional"))
    )
    (net (code "34") (name "Net-(PIC32-AN2{slash}C2IN-{slash}CN4{slash}RB2)") (class "Default")
      (node (ref "PIC32") (pin "14") (pinfunction "AN2/C2IN-/CN4/RB2_14") (pintype "bidirectional"))
      (node (ref "R20") (pin "1") (pinfunction "1_1") (pintype "passive"))
    )
    (net (code "35") (name "Net-(PIC32-AN3{slash}C2IN+{slash}CN5{slash}RB3)") (class "Default")
      (node (ref "PIC32") (pin "13") (pinfunction "AN3/C2IN+/CN5/RB3_13") (pintype "bidirectional"))
      (node (ref "R23") (pin "1") (pinfunction "1_1") (pintype "passive"))
    )
    (net (code "36") (name "Net-(PIC32-AN4{slash}C1IN-{slash}CN6{slash}RB4)") (class "Default")
      (node (ref "PIC32") (pin "12") (pinfunction "AN4/C1IN-/CN6/RB4_12") (pintype "bidirectional"))
      (node (ref "R24") (pin "1") (pinfunction "1_1") (pintype "passive"))
    )
    (net (code "37") (name "Net-(PIC32-AN5{slash}C1IN+{slash}VBUSON{slash}CN7{slash}RB5)") (class "Default")
      (node (ref "PIC32") (pin "11") (pinfunction "AN5/C1IN+/VBUSON/CN7/RB5_11") (pintype "bidirectional"))
      (node (ref "R25") (pin "1") (pinfunction "1_1") (pintype "passive"))
    )
    (net (code "38") (name "Net-(PIC32-AN8{slash}~{SS4{slash}U5RX{slash}}U2CTS{slash}C1OUT{slash}RB8)") (class "Default")
      (node (ref "PIC32") (pin "21") (pinfunction "AN8/~{SS4/U5RX/}U2CTS/C1OUT/RB8_21") (pintype "bidirectional"))
      (node (ref "U$5") (pin "1") (pinfunction "1_1") (pintype "passive"))
    )
    (net (code "39") (name "Net-(PIC32-AN9{slash}C2OUT{slash}PMA7{slash}RB9)") (class "Default")
      (node (ref "PIC32") (pin "22") (pinfunction "AN9/C2OUT/PMA7/RB9_22") (pintype "bidirectional"))
      (node (ref "R10") (pin "2") (pinfunction "2_2") (pintype "passive"))
    )
    (net (code "40") (name "Net-(PIC32-AN14{slash}SCK4{slash}U5TX{slash}~{U2RTSU2RTS{slash}PMALH{slash}PMA1{slash}RB14})") (class "Default")
      (node (ref "PIC32") (pin "29") (pinfunction "AN14/SCK4/U5TX/~{U2RTSU2RTS/PMALH/PMA1/RB14}_29") (pintype "bidirectional"))
      (node (ref "U$6") (pin "1") (pinfunction "1_1") (pintype "passive"))
    )
    (net (code "41") (name "Net-(PIC32-AVDD)") (class "Default")
      (node (ref "C16") (pin "2") (pinfunction "2_2") (pintype "passive"))
      (node (ref "PIC32") (pin "19") (pinfunction "AVDD_19") (pintype "power_in"))
      (node (ref "R1") (pin "1") (pinfunction "1_1") (pintype "passive"))
    )
    (net (code "42") (name "Net-(PIC32-OC1{slash}INT0{slash}RD0)") (class "Default")
      (node (ref "PIC32") (pin "46") (pinfunction "OC1/INT0/RD0_46") (pintype "bidirectional"))
      (node (ref "R4") (pin "1") (pinfunction "1_1") (pintype "passive"))
    )
    (net (code "43") (name "Net-(PIC32-OSC1{slash}CLKI{slash}RC12)") (class "Default")
      (node (ref "C17") (pin "1") (pinfunction "1_1") (pintype "passive"))
      (node (ref "ECS-240-20-33-TR1") (pin "1") (pinfunction "1_1") (pintype "bidirectional"))
      (node (ref "PIC32") (pin "39") (pinfunction "OSC1/CLKI/RC12_39") (pintype "bidirectional"))
    )
    (net (code "44") (name "Net-(PIC32-OSC2{slash}CLKO{slash}RC15)") (class "Default")
      (node (ref "C18") (pin "2") (pinfunction "2_2") (pintype "passive"))
      (node (ref "ECS-240-20-33-TR1") (pin "3") (pinfunction "3_3") (pintype "bidirectional"))
      (node (ref "PIC32") (pin "40") (pinfunction "OSC2/CLKO/RC15_40") (pintype "bidirectional"))
    )
    (net (code "45") (name "Net-(PIC32-PGEC1{slash}AN1{slash}VREF-{slash}CVREF-{slash}CN3{slash}RB1)") (class "Default")
      (node (ref "PIC32") (pin "15") (pinfunction "PGEC1/AN1/VREF-/CVREF-/CN3/RB1_15") (pintype "bidirectional"))
      (node (ref "PIC_PROG1") (pin "5") (pinfunction "5_5") (pintype "passive"))
    )
    (net (code "46") (name "Net-(PIC32-PGEC2{slash}AN6{slash}OCFA{slash}RB6)") (class "Default")
      (node (ref "PIC32") (pin "17") (pinfunction "PGEC2/AN6/OCFA/RB6_17") (pintype "bidirectional"))
      (node (ref "R26") (pin "1") (pinfunction "1_1") (pintype "passive"))
    )
    (net (code "47") (name "Net-(PIC32-PGED1{slash}AN0{slash}VREF+{slash}CVREF+{slash}PMA6{slash}CN2{slash}RB0)") (class "Default")
      (node (ref "PIC32") (pin "16") (pinfunction "PGED1/AN0/VREF+/CVREF+/PMA6/CN2/RB0_16") (pintype "bidirectional"))
      (node (ref "PIC_PROG1") (pin "4") (pinfunction "4_4") (pintype "passive"))
    )
    (net (code "48") (name "Net-(PIC32-SCK2A{slash}U3BTX{slash}~{U3ARTS{slash}PMA5{slash}CN8{slash}RG6})") (class "Default")
      (node (ref "PIC32") (pin "4") (pinfunction "SCK2A/U3BTX/~{U3ARTS/PMA5/CN8/RG6}_4") (pintype "bidirectional"))
      (node (ref "TOUCHSCREEN") (pin "1") (pinfunction "1_1") (pintype "bidirectional"))
    )
    (net (code "49") (name "Net-(PIC32-SCK3{slash}U4TX{slash}U1RTS{slash}OC2{slash}RD1)") (class "Default")
      (node (ref "LIDAR") (pin "3") (pinfunction "3_3") (pintype "passive"))
      (node (ref "PIC32") (pin "49") (pinfunction "SCK3/U4TX/U1RTS/OC2/RD1_49") (pintype "bidirectional"))
      (node (ref "UARTRX4") (pin "C") (pinfunction "C_C") (pintype "passive"))
    )
    (net (code "50") (name "Net-(PIC32-SCL3{slash}SDO3{slash}U1TX{slash}OC4{slash}RD3)") (class "Default")
      (node (ref "I2C2") (pin "2") (pinfunction "2_2") (pintype "passive"))
      (node (ref "PIC32") (pin "51") (pinfunction "SCL3/SDO3/U1TX/OC4/RD3_51") (pintype "bidirectional"))
    )
    (net (code "51") (name "Net-(PIC32-SCL4{slash}SDO2{slash}U3TX{slash}PMA3{slash}CN10{slash}RG8)") (class "Default")
      (node (ref "PIC32") (pin "6") (pinfunction "SCL4/SDO2/U3TX/PMA3/CN10/RG8_6") (pintype "bidirectional"))
      (node (ref "TOUCHSCREEN") (pin "5") (pinfunction "5_5") (pintype "bidirectional"))
      (node (ref "U$4") (pin "2") (pinfunction "2_2") (pintype "passive"))
    )
    (net (code "52") (name "Net-(PIC32-SDA2A{slash}SDI2A{slash}U3ARX{slash}PMA4{slash}CN9{slash}RG7)") (class "Default")
      (node (ref "PIC32") (pin "5") (pinfunction "SDA2A/SDI2A/U3ARX/PMA4/CN9/RG7_5") (pintype "bidirectional"))
      (node (ref "TOUCHSCREEN") (pin "3") (pinfunction "3_3") (pintype "bidirectional"))
    )
    (net (code "53") (name "Net-(PIC32-SDA3{slash}SDI3{slash}U1RX{slash}OC3{slash}RD2)") (class "Default")
      (node (ref "I2C2") (pin "1") (pinfunction "1_1") (pintype "passive"))
      (node (ref "PIC32") (pin "50") (pinfunction "SDA3/SDI3/U1RX/OC3/RD2_50") (pintype "bidirectional"))
    )
    (net (code "54") (name "Net-(PIC32-TDO{slash}AN11{slash}PMA12{slash}RB11)") (class "Default")
      (node (ref "PIC32") (pin "24") (pinfunction "TDO/AN11/PMA12/RB11_24") (pintype "bidirectional"))
      (node (ref "R11") (pin "2") (pinfunction "2_2") (pintype "passive"))
    )
    (net (code "55") (name "Net-(PIC32-TMS{slash}AN10{slash}CVREFOUT{slash}PMA13{slash}RB10)") (class "Default")
      (node (ref "PIC32") (pin "23") (pinfunction "TMS/AN10/CVREFOUT/PMA13/RB10_23") (pintype "bidirectional"))
      (node (ref "R2") (pin "2") (pinfunction "2_2") (pintype "passive"))
    )
    (net (code "56") (name "Net-(PIC32-VCAP{slash}VDDCORE)") (class "Default")
      (node (ref "C20") (pin "2") (pinfunction "2_2") (pintype "passive"))
      (node (ref "C21") (pin "2") (pinfunction "2_2") (pintype "passive"))
      (node (ref "PIC32") (pin "56") (pinfunction "VCAP/VDDCORE_56") (pintype "power_in"))
    )
    (net (code "57") (name "Net-(PIC32-~{SS2{slash}U6RX{slash}}U3CTS{slash}PMA2{slash}CN11{slash}RG9)") (class "Default")
      (node (ref "PIC32") (pin "8") (pinfunction "~{SS2/U6RX/}U3CTS/PMA2/CN11/RG9_8") (pintype "bidirectional"))
      (node (ref "TOUCHSCREEN") (pin "4") (pinfunction "4_4") (pintype "bidirectional"))
      (node (ref "U$3") (pin "2") (pinfunction "2_2") (pintype "passive"))
    )
    (net (code "58") (name "Net-(PIC32-~{SS3{slash}U4RX{slash}}U1CTS{slash}SDA1{slash}IC2{slash}INT2{slash}RD9)") (class "Default")
      (node (ref "LIDAR") (pin "2") (pinfunction "2_2") (pintype "passive"))
      (node (ref "PIC32") (pin "43") (pinfunction "~{SS3/U4RX/}U1CTS/SDA1/IC2/INT2/RD9_43") (pintype "bidirectional"))
      (node (ref "UARTTX4") (pin "C") (pinfunction "C_C") (pintype "passive"))
    )
    (net (code "59") (name "Net-(POWER-PadA)") (class "Default")
      (node (ref "POWER") (pin "A") (pinfunction "A_A") (pintype "passive"))
      (node (ref "R39") (pin "2") (pinfunction "2_2") (pintype "passive"))
    )
    (net (code "60") (name "Net-(Q1-D)") (class "Default")
      (node (ref "Q1") (pin "3") (pinfunction "D_3") (pintype "passive"))
      (node (ref "R3") (pin "2") (pinfunction "2_2") (pintype "passive"))
      (node (ref "SERVO1") (pin "3") (pinfunction "3_3") (pintype "passive"))
    )
    (net (code "61") (name "Net-(Q1-G)") (class "Default")
      (node (ref "Q1") (pin "1") (pinfunction "G_1") (pintype "passive"))
      (node (ref "R5") (pin "1") (pinfunction "1_1") (pintype "passive"))
    )
    (net (code "62") (name "Net-(Q2-D)") (class "Default")
      (node (ref "Q2") (pin "3") (pinfunction "D_3") (pintype "passive"))
      (node (ref "R22") (pin "2") (pinfunction "2_2") (pintype "passive"))
      (node (ref "SERVO2") (pin "3") (pinfunction "3_3") (pintype "passive"))
    )
    (net (code "63") (name "Net-(Q2-G)") (class "Default")
      (node (ref "Q2") (pin "1") (pinfunction "G_1") (pintype "passive"))
      (node (ref "R21") (pin "1") (pinfunction "1_1") (pintype "passive"))
    )
    (net (code "64") (name "Net-(R6-Pad1)") (class "Default")
      (node (ref "R6") (pin "1") (pinfunction "1_1") (pintype "passive"))
      (node (ref "WLAN") (pin "A") (pinfunction "A_A") (pintype "passive"))
    )
    (net (code "65") (name "Net-(R7-Pad1)") (class "Default")
      (node (ref "R7") (pin "1") (pinfunction "1_1") (pintype "passive"))
      (node (ref "S1") (pin "3") (pinfunction "3_3") (pintype "passive"))
    )
    (net (code "66") (name "Net-(R18-Pad1)") (class "Default")
      (node (ref "R18") (pin "1") (pinfunction "1_1") (pintype "passive"))
      (node (ref "UARTRX4") (pin "A") (pinfunction "A_A") (pintype "passive"))
    )
    (net (code "67") (name "Net-(R19-Pad1)") (class "Default")
      (node (ref "R19") (pin "1") (pinfunction "1_1") (pintype "passive"))
      (node (ref "UARTTX4") (pin "A") (pinfunction "A_A") (pintype "passive"))
    )
    (net (code "68") (name "Net-(U$1-OUT1)") (class "Default")
      (node (ref "JP3") (pin "1") (pinfunction "1_1") (pintype "passive"))
      (node (ref "U$1") (pin "16") (pinfunction "OUT1_16") (pintype "bidirectional"))
    )
    (net (code "69") (name "Net-(U$1-OUT2)") (class "Default")
      (node (ref "JP3") (pin "2") (pinfunction "2_2") (pintype "passive"))
      (node (ref "U$1") (pin "15") (pinfunction "OUT2_15") (pintype "bidirectional"))
    )
    (net (code "70") (name "Net-(U$1-OUT3)") (class "Default")
      (node (ref "JP3") (pin "3") (pinfunction "3_3") (pintype "passive"))
      (node (ref "U$1") (pin "14") (pinfunction "OUT3_14") (pintype "bidirectional"))
    )
    (net (code "71") (name "Net-(U$1-OUT4)") (class "Default")
      (node (ref "JP3") (pin "4") (pinfunction "4_4") (pintype "passive"))
      (node (ref "U$1") (pin "13") (pinfunction "OUT4_13") (pintype "bidirectional"))
    )
    (net (code "72") (name "Net-(U$1-OUT5)") (class "Default")
      (node (ref "JP2") (pin "1") (pinfunction "1_1") (pintype "passive"))
      (node (ref "U$1") (pin "12") (pinfunction "OUT5_12") (pintype "bidirectional"))
    )
    (net (code "73") (name "Net-(U$1-OUT6)") (class "Default")
      (node (ref "JP2") (pin "2") (pinfunction "2_2") (pintype "passive"))
      (node (ref "U$1") (pin "11") (pinfunction "OUT6_11") (pintype "bidirectional"))
    )
    (net (code "74") (name "Net-(U$1-OUT7)") (class "Default")
      (node (ref "JP2") (pin "3") (pinfunction "3_3") (pintype "passive"))
      (node (ref "U$1") (pin "10") (pinfunction "OUT7_10") (pintype "bidirectional"))
    )
    (net (code "75") (name "Net-(U$2-OUT1)") (class "Default")
      (node (ref "JP2") (pin "4") (pinfunction "4_4") (pintype "passive"))
      (node (ref "U$2") (pin "16") (pinfunction "OUT1_16") (pintype "bidirectional"))
    )
    (net (code "76") (name "Net-(U$2-OUT2)") (class "Default")
      (node (ref "JP1") (pin "1") (pinfunction "1_1") (pintype "passive"))
      (node (ref "U$2") (pin "15") (pinfunction "OUT2_15") (pintype "bidirectional"))
    )
    (net (code "77") (name "Net-(U$2-OUT3)") (class "Default")
      (node (ref "JP1") (pin "2") (pinfunction "2_2") (pintype "passive"))
      (node (ref "U$2") (pin "14") (pinfunction "OUT3_14") (pintype "bidirectional"))
    )
    (net (code "78") (name "Net-(U$2-OUT4)") (class "Default")
      (node (ref "JP1") (pin "3") (pinfunction "3_3") (pintype "passive"))
      (node (ref "U$2") (pin "13") (pinfunction "OUT4_13") (pintype "bidirectional"))
    )
    (net (code "79") (name "Net-(U$2-OUT5)") (class "Default")
      (node (ref "JP1") (pin "4") (pinfunction "4_4") (pintype "passive"))
      (node (ref "U$2") (pin "12") (pinfunction "OUT5_12") (pintype "bidirectional"))
    )
    (net (code "80") (name "Net-(U2-ELED1)") (class "Default")
      (node (ref "LED7") (pin "C") (pinfunction "C_C") (pintype "passive"))
      (node (ref "U2") (pin "18") (pinfunction "ELED1_18") (pintype "bidirectional"))
    )
    (net (code "81") (name "Net-(U2-ELED2)") (class "Default")
      (node (ref "LED6") (pin "C") (pinfunction "C_C") (pintype "passive"))
      (node (ref "U2") (pin "20") (pinfunction "ELED2_20") (pintype "bidirectional"))
    )
    (net (code "82") (name "Net-(U2-RX1)") (class "Default")
      (node (ref "U$6") (pin "2") (pinfunction "2_2") (pintype "passive"))
      (node (ref "U2") (pin "9") (pinfunction "RX1_9") (pintype "bidirectional"))
    )
    (net (code "83") (name "Net-(U2-RX2)") (class "Default")
      (node (ref "U$4") (pin "1") (pinfunction "1_1") (pintype "passive"))
      (node (ref "U2") (pin "25") (pinfunction "RX2_25") (pintype "bidirectional"))
    )
    (net (code "84") (name "Net-(U2-TX1)") (class "Default")
      (node (ref "U$5") (pin "2") (pinfunction "2_2") (pintype "passive"))
      (node (ref "U2") (pin "5") (pinfunction "TX1_5") (pintype "bidirectional"))
    )
    (net (code "85") (name "Net-(U2-TX2)") (class "Default")
      (node (ref "U$3") (pin "1") (pinfunction "1_1") (pintype "passive"))
      (node (ref "U2") (pin "21") (pinfunction "TX2_21") (pintype "bidirectional"))
    )
    (net (code "86") (name "Net-(U2-WLANLED)") (class "Default")
      (node (ref "U2") (pin "22") (pinfunction "WLANLED_22") (pintype "bidirectional"))
      (node (ref "WLAN") (pin "C") (pinfunction "C_C") (pintype "passive"))
    )
    (net (code "87") (name "Net-(U3-OUTB)") (class "Default")
      (node (ref "C3") (pin "2") (pinfunction "2_2") (pintype "passive"))
      (node (ref "F1") (pin "2") (pinfunction "2_2") (pintype "passive"))
      (node (ref "U3") (pin "5") (pinfunction "OUTB_5") (pintype "bidirectional"))
    )
    (net (code "88") (name "SERV1") (class "Default")
      (node (ref "PIC32") (pin "28") (pinfunction "TDI/AN13/PMA10/RB13_28") (pintype "bidirectional"))
      (node (ref "Q1") (pin "2") (pinfunction "S_2") (pintype "passive"))
      (node (ref "R13") (pin "2") (pinfunction "2_2") (pintype "passive"))
      (node (ref "R16") (pin "1") (pinfunction "1_1") (pintype "passive"))
    )
    (net (code "89") (name "SERV2") (class "Default")
      (node (ref "PIC32") (pin "27") (pinfunction "TCK/AN12/PMA11/RB12_27") (pintype "bidirectional"))
      (node (ref "Q2") (pin "2") (pinfunction "S_2") (pintype "passive"))
      (node (ref "R12") (pin "2") (pinfunction "2_2") (pintype "passive"))
      (node (ref "R17") (pin "1") (pinfunction "1_1") (pintype "passive"))
    )
    (net (code "90") (name "VCC") (class "Default")
      (node (ref "3.3V_REG") (pin "1") (pinfunction "CTL_1") (pintype "bidirectional"))
      (node (ref "3.3V_REG") (pin "2") (pinfunction "VCC_2") (pintype "bidirectional"))
      (node (ref "C4") (pin "1") (pinfunction "1_1") (pintype "passive"))
      (node (ref "C5") (pin "A") (pinfunction "+_A") (pintype "passive"))
      (node (ref "C7") (pin "1") (pinfunction "1_1") (pintype "passive"))
      (node (ref "D1") (pin "C") (pinfunction "C_C") (pintype "passive"))
      (node (ref "F4") (pin "1") (pinfunction "1_1") (pintype "passive"))
      (node (ref "R39") (pin "1") (pinfunction "1_1") (pintype "passive"))
      (node (ref "U1") (pin "1") (pinfunction "CTL_1") (pintype "bidirectional"))
      (node (ref "U1") (pin "2") (pinfunction "VCC_2") (pintype "bidirectional"))
    )
    (net (code "91") (name "VUSB") (class "Default")
      (node (ref "PIC32") (pin "35") (pinfunction "VUSB_35") (pintype "power_in"))
    )
    (net (code "92") (name "unconnected-(PIC32-AN15{slash}OCFB{slash}PMALL{slash}PMA0{slash}CN12{slash}RB15-Pad30)") (class "Default")
      (node (ref "PIC32") (pin "30") (pinfunction "AN15/OCFB/PMALL/PMA0/CN12/RB15_30") (pintype "bidirectional"))
    )
    (net (code "93") (name "unconnected-(PIC32-C1RX{slash}RF0-Pad58)") (class "Default")
      (node (ref "PIC32") (pin "58") (pinfunction "C1RX/RF0_58") (pintype "bidirectional"))
    )
    (net (code "94") (name "unconnected-(PIC32-C1TX{slash}RF1-Pad59)") (class "Default")
      (node (ref "PIC32") (pin "59") (pinfunction "C1TX/RF1_59") (pintype "bidirectional"))
    )
    (net (code "95") (name "unconnected-(PIC32-D+{slash}RG2-Pad37)") (class "Default")
      (node (ref "PIC32") (pin "37") (pinfunction "D+/RG2_37") (pintype "bidirectional"))
    )
    (net (code "96") (name "unconnected-(PIC32-D-{slash}RG3-Pad36)") (class "Default")
      (node (ref "PIC32") (pin "36") (pinfunction "D-/RG3_36") (pintype "bidirectional"))
    )
    (net (code "97") (name "unconnected-(PIC32-IC4{slash}PMCS1{slash}PMA14{slash}INT4{slash}RD11-Pad45)") (class "Default")
      (node (ref "PIC32") (pin "45") (pinfunction "IC4/PMCS1/PMA14/INT4/RD11_45") (pintype "bidirectional"))
    )
    (net (code "98") (name "unconnected-(PIC32-PGED2{slash}AN7{slash}RB7-Pad18)") (class "Default")
      (node (ref "PIC32") (pin "18") (pinfunction "PGED2/AN7/RB7_18") (pintype "bidirectional"))
    )
    (net (code "99") (name "unconnected-(PIC32-RTCC{slash}IC1{slash}INT1{slash}RD8-Pad42)") (class "Default")
      (node (ref "PIC32") (pin "42") (pinfunction "RTCC/IC1/INT1/RD8_42") (pintype "bidirectional"))
    )
    (net (code "100") (name "unconnected-(PIC32-SCL1{slash}IC3{slash}PMCS2{slash}PMA15{slash}INT3{slash}RD10-Pad44)") (class "Default")
      (node (ref "PIC32") (pin "44") (pinfunction "SCL1/IC3/PMCS2/PMA15/INT3/RD10_44") (pintype "bidirectional"))
    )
    (net (code "101") (name "unconnected-(PIC32-SOSCI{slash}CN1{slash}RC13-Pad47)") (class "Default")
      (node (ref "PIC32") (pin "47") (pinfunction "SOSCI/CN1/RC13_47") (pintype "bidirectional"))
    )
    (net (code "102") (name "unconnected-(PIC32-SOSCO{slash}T1CK{slash}CN0{slash}RC14-Pad48)") (class "Default")
      (node (ref "PIC32") (pin "48") (pinfunction "SOSCO/T1CK/CN0/RC14_48") (pintype "bidirectional"))
    )
    (net (code "103") (name "unconnected-(PIC32-USBID{slash}RF3-Pad33)") (class "Default")
      (node (ref "PIC32") (pin "33") (pinfunction "USBID/RF3_33") (pintype "bidirectional"))
    )
    (net (code "104") (name "unconnected-(PIC32-VBUS-Pad34)") (class "Default")
      (node (ref "PIC32") (pin "34") (pinfunction "VBUS_34") (pintype "input"))
    )
    (net (code "105") (name "unconnected-(S1-Pad2)") (class "Default")
      (node (ref "S1") (pin "2") (pinfunction "2_2") (pintype "passive"))
    )
    (net (code "106") (name "unconnected-(S1-Pad4)") (class "Default")
      (node (ref "S1") (pin "4") (pinfunction "4_4") (pintype "passive"))
    )
    (net (code "107") (name "unconnected-(U$2-IN6-Pad6)") (class "Default")
      (node (ref "U$2") (pin "6") (pinfunction "IN6_6") (pintype "bidirectional"))
    )
    (net (code "108") (name "unconnected-(U$2-IN7-Pad7)") (class "Default")
      (node (ref "U$2") (pin "7") (pinfunction "IN7_7") (pintype "bidirectional"))
    )
    (net (code "109") (name "unconnected-(U$2-OUT6-Pad11)") (class "Default")
      (node (ref "U$2") (pin "11") (pinfunction "OUT6_11") (pintype "bidirectional"))
    )
    (net (code "110") (name "unconnected-(U$2-OUT7-Pad10)") (class "Default")
      (node (ref "U$2") (pin "10") (pinfunction "OUT7_10") (pintype "bidirectional"))
    )
    (net (code "111") (name "unconnected-(U2-CP1-Pad13)") (class "Default")
      (node (ref "U2") (pin "13") (pinfunction "CP1_13") (pintype "bidirectional"))
    )
    (net (code "112") (name "unconnected-(U2-CP2-Pad15)") (class "Default")
      (node (ref "U2") (pin "15") (pinfunction "CP2_15") (pintype "bidirectional"))
    )
    (net (code "113") (name "unconnected-(U2-CP3-Pad17)") (class "Default")
      (node (ref "U2") (pin "17") (pinfunction "CP3_17") (pintype "bidirectional"))
    )
    (net (code "114") (name "unconnected-(U2-CP4-Pad19)") (class "Default")
      (node (ref "U2") (pin "19") (pinfunction "CP4_19") (pintype "bidirectional"))
    )
    (net (code "115") (name "unconnected-(U2-CP5-Pad29)") (class "Default")
      (node (ref "U2") (pin "29") (pinfunction "CP5_29") (pintype "bidirectional"))
    )
    (net (code "116") (name "unconnected-(U2-CP6-Pad31)") (class "Default")
      (node (ref "U2") (pin "31") (pinfunction "CP6_31") (pintype "bidirectional"))
    )
    (net (code "117") (name "unconnected-(U2-CP7-Pad33)") (class "Default")
      (node (ref "U2") (pin "33") (pinfunction "CP7_33") (pintype "bidirectional"))
    )
    (net (code "118") (name "unconnected-(U2-CP8-Pad35)") (class "Default")
      (node (ref "U2") (pin "35") (pinfunction "CP8_35") (pintype "bidirectional"))
    )
    (net (code "119") (name "unconnected-(U2-CTS1-Pad11)") (class "Default")
      (node (ref "U2") (pin "11") (pinfunction "CTS1_11") (pintype "bidirectional"))
    )
    (net (code "120") (name "unconnected-(U2-CTS2-Pad27)") (class "Default")
      (node (ref "U2") (pin "27") (pinfunction "CTS2_27") (pintype "bidirectional"))
    )
    (net (code "121") (name "unconnected-(U2-RTS1-Pad7)") (class "Default")
      (node (ref "U2") (pin "7") (pinfunction "RTS1_7") (pintype "bidirectional"))
    )
    (net (code "122") (name "unconnected-(U2-RTS2-Pad23)") (class "Default")
      (node (ref "U2") (pin "23") (pinfunction "RTS2_23") (pintype "bidirectional"))
    )
    (net (code "123") (name "unconnected-(U2-RX+-Pad14)") (class "Default")
      (node (ref "U2") (pin "14") (pinfunction "RX+_14") (pintype "bidirectional"))
    )
    (net (code "124") (name "unconnected-(U2-RX--Pad16)") (class "Default")
      (node (ref "U2") (pin "16") (pinfunction "RX-_16") (pintype "bidirectional"))
    )
    (net (code "125") (name "unconnected-(U2-RXCT-Pad12)") (class "Default")
      (node (ref "U2") (pin "12") (pinfunction "RXCT_12") (pintype "bidirectional"))
    )
    (net (code "126") (name "unconnected-(U2-TX+-Pad6)") (class "Default")
      (node (ref "U2") (pin "6") (pinfunction "TX+_6") (pintype "bidirectional"))
    )
    (net (code "127") (name "unconnected-(U2-TX--Pad8)") (class "Default")
      (node (ref "U2") (pin "8") (pinfunction "TX-_8") (pintype "bidirectional"))
    )
    (net (code "128") (name "unconnected-(U2-TXCT-Pad10)") (class "Default")
      (node (ref "U2") (pin "10") (pinfunction "TXCT_10") (pintype "bidirectional"))
    )
    (net (code "129") (name "unconnected-(U2-~{RESET}-Pad1)") (class "Default")
      (node (ref "U2") (pin "1") (pinfunction "~{RESET}_1") (pintype "bidirectional"))
    )
    (net (code "130") (name "unconnected-(U3-INA-Pad2)") (class "Default")
      (node (ref "U3") (pin "2") (pinfunction "INA_2") (pintype "bidirectional"))
    )
    (net (code "131") (name "unconnected-(U3-OUTA-Pad7)") (class "Default")
      (node (ref "U3") (pin "7") (pinfunction "OUTA_7") (pintype "bidirectional"))
    )
    (net (code "132") (name "~{MCLR}") (class "Default")
      (node (ref "C19") (pin "1") (pinfunction "1_1") (pintype "passive"))
      (node (ref "PIC32") (pin "7") (pinfunction "~{MCLR}_7") (pintype "input"))
      (node (ref "PIC_PROG1") (pin "1") (pinfunction "1_1") (pintype "passive"))
      (node (ref "R7") (pin "2") (pinfunction "2_2") (pintype "passive"))
      (node (ref "R9") (pin "1") (pinfunction "1_1") (pintype "passive"))
    )
  )
)
